# MRCS-Dual-3-Position-Semaphore-Controlle.net
KiCad netlist of a schematic drawn in EAGLE
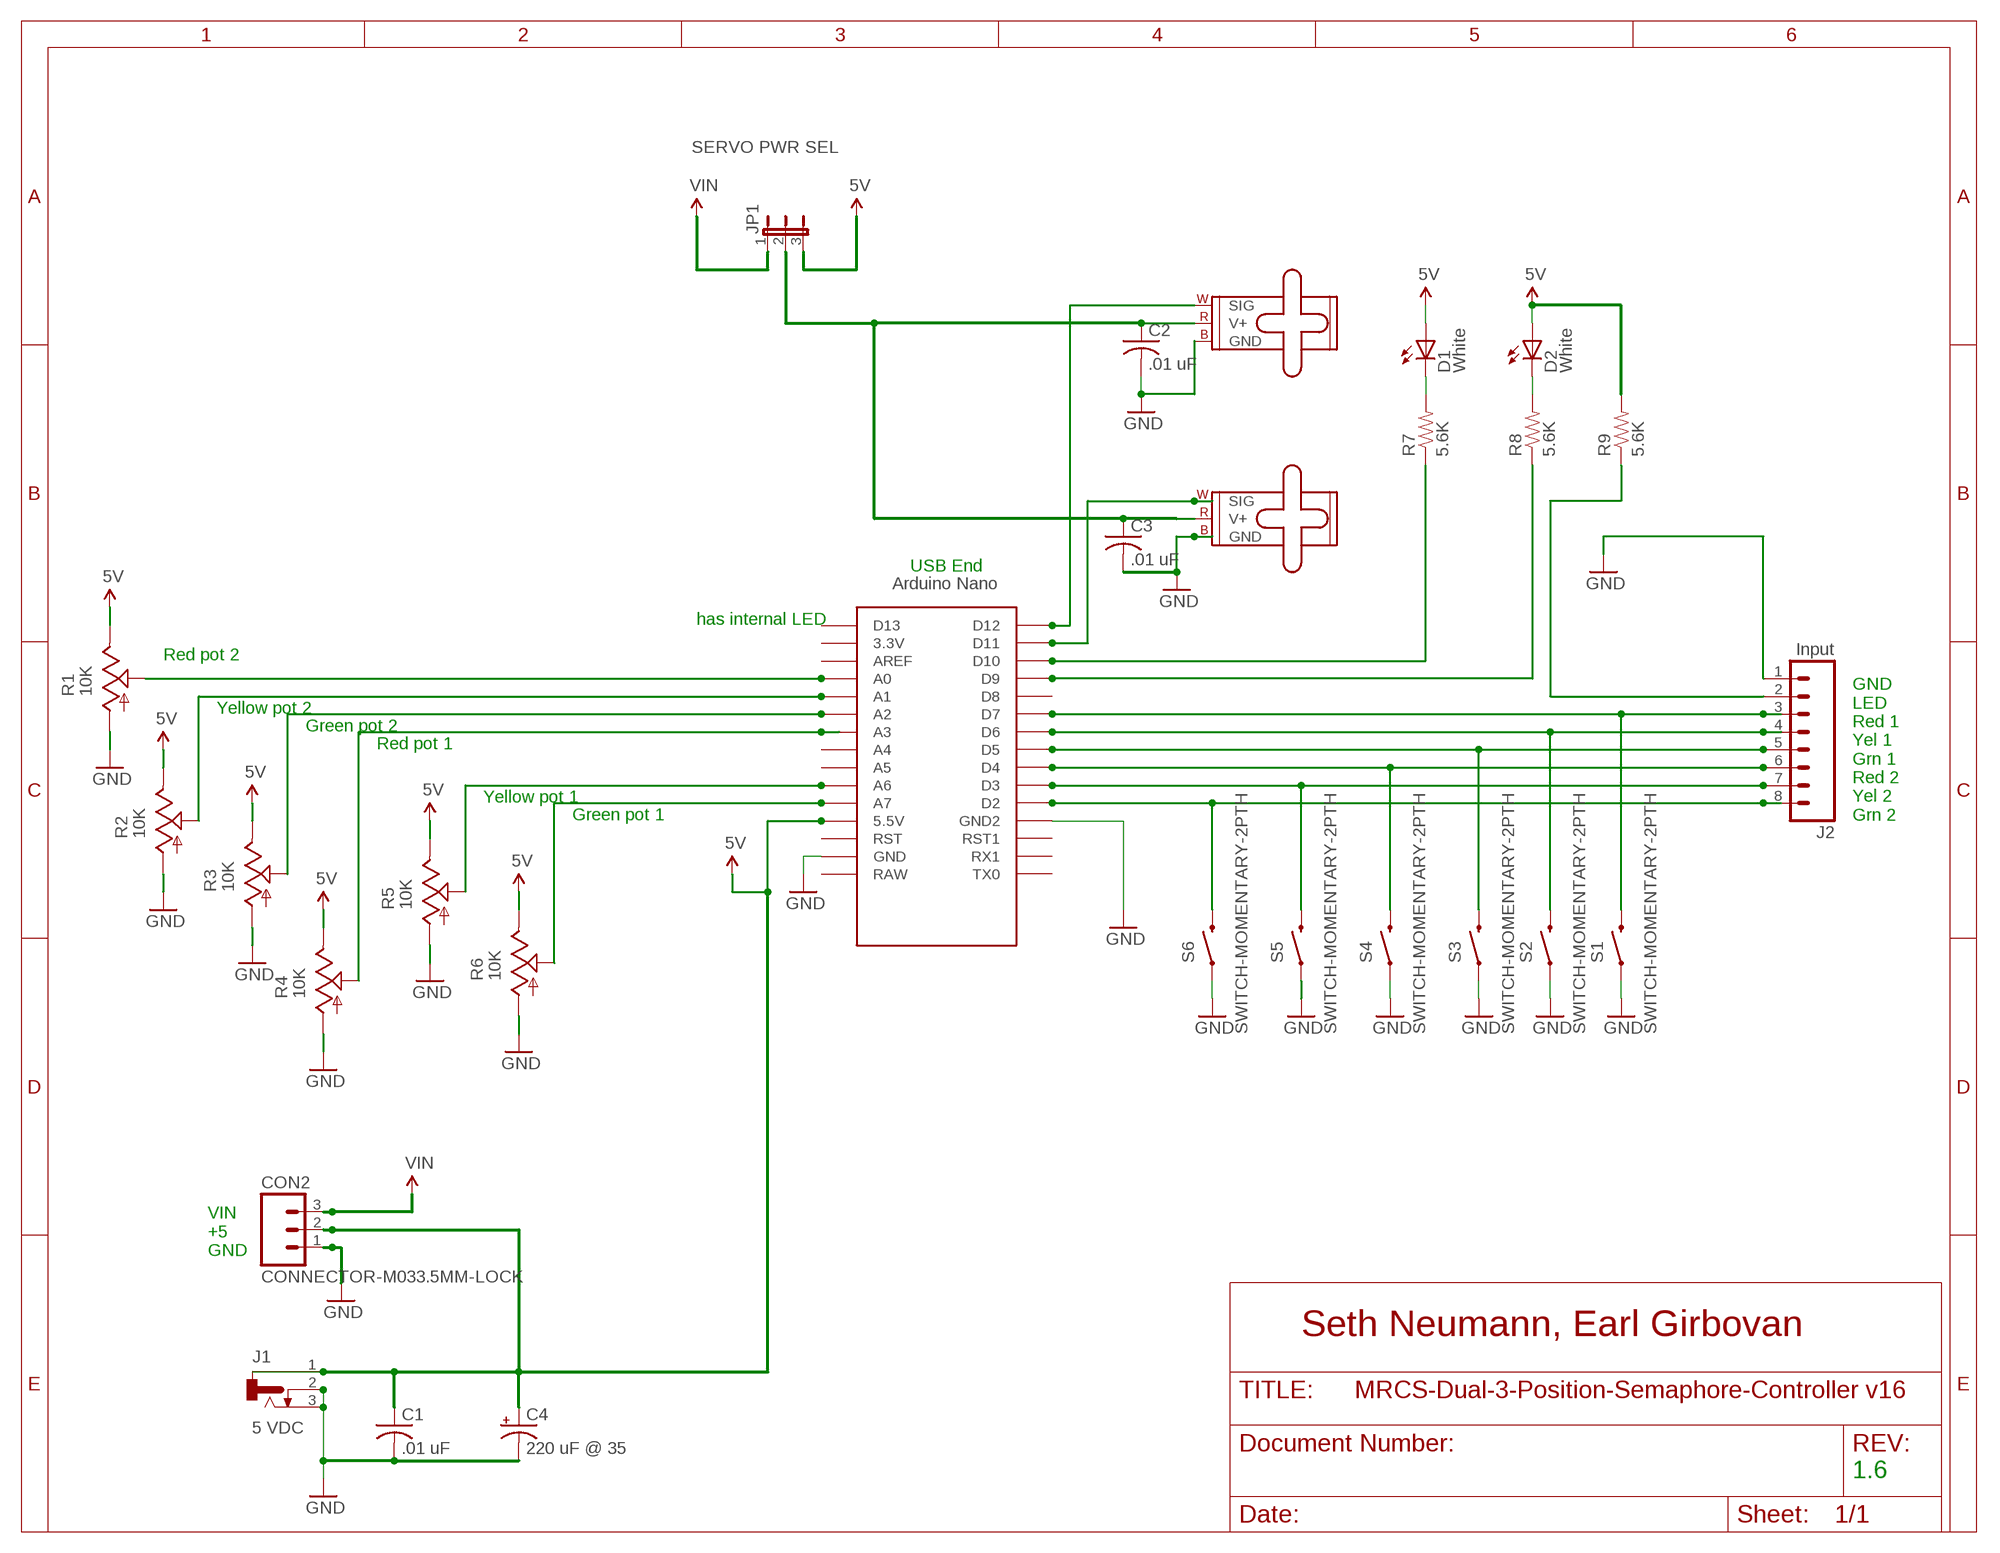
[diagram p0: schematic, sheet 1]

(export (version "E")
  (design (tool "Eeschema 10.0.6"))
  (components
    (comp (ref "C1")
      (value ".01 uF")
      (footprint "eagle-import:C050-024X044")
      (libsource (lib "eagle-import") (part "CAPPTH1"))
    )
    (comp (ref "C2")
      (value ".01 uF")
      (footprint "eagle-import:C050-024X044")
      (libsource (lib "eagle-import") (part "CAPPTH1"))
    )
    (comp (ref "C3")
      (value ".01 uF")
      (footprint "eagle-import:C050-024X044")
      (libsource (lib "eagle-import") (part "CAPPTH1"))
    )
    (comp (ref "C4")
      (value "220 uF @ 35")
      (footprint "eagle-import:E5-10.5")
      (libsource (lib "eagle-import") (part "CAP-POLPTH-5MM"))
    )
    (comp (ref "CON2")
      (value "CONNECTOR-M033.5MM-LOCK")
      (footprint "eagle-import:SCREWTERMINAL-3.5MM-3_LOCK.007S")
      (libsource (lib "eagle-import") (part "CONNECTOR-M033.5MM-LOCK"))
    )
    (comp (ref "D1")
      (value "White")
      (footprint "eagle-import:LED3MM")
      (libsource (lib "eagle-import") (part "LEDLED3MM"))
    )
    (comp (ref "D2")
      (value "White")
      (footprint "eagle-import:LED3MM")
      (libsource (lib "eagle-import") (part "LEDLED3MM"))
    )
    (comp (ref "J1")
      (value "5 VDC")
      (footprint "eagle-import:DCJ0202")
      (libsource (lib "eagle-import") (part "CONNECTOR-DC-POWER-RA"))
    )
    (comp (ref "J2")
      (value "Input")
      (footprint "eagle-import:1X08_LOCK")
      (libsource (lib "eagle-import") (part "CONNECTOR-M08LOCK"))
    )
    (comp (ref "JP1")
      (value "SERVO PWR SEL")
      (footprint "eagle-import:1X03")
      (libsource (lib "eagle-import") (part "JUMPER-3PTH-LOCK"))
    )
    (comp (ref "M1")
      (value "SMALL_SERVO")
      (footprint "eagle-import:1X03")
      (libsource (lib "eagle-import") (part "SMALL_SERVO"))
    )
    (comp (ref "M2")
      (value "SMALL_SERVO")
      (footprint "eagle-import:1X03")
      (libsource (lib "eagle-import") (part "SMALL_SERVO"))
    )
    (comp (ref "NANO")
      (value "NANO")
      (footprint "eagle-import:NANO")
      (libsource (lib "eagle-import") (part "NANO"))
    )
    (comp (ref "R1")
      (value "10K")
      (footprint "eagle-import:RS3")
      (libsource (lib "eagle-import") (part "TRIM_US-RS3"))
    )
    (comp (ref "R2")
      (value "10K")
      (footprint "eagle-import:RS3")
      (libsource (lib "eagle-import") (part "TRIM_US-RS3"))
    )
    (comp (ref "R3")
      (value "10K")
      (footprint "eagle-import:RS3")
      (libsource (lib "eagle-import") (part "TRIM_US-RS3"))
    )
    (comp (ref "R4")
      (value "10K")
      (footprint "eagle-import:RS3")
      (libsource (lib "eagle-import") (part "TRIM_US-RS3"))
    )
    (comp (ref "R5")
      (value "10K")
      (footprint "eagle-import:RS3")
      (libsource (lib "eagle-import") (part "TRIM_US-RS3"))
    )
    (comp (ref "R6")
      (value "10K")
      (footprint "eagle-import:RS3")
      (libsource (lib "eagle-import") (part "TRIM_US-RS3"))
    )
    (comp (ref "R7")
      (value "5.6K")
      (footprint "eagle-import:AXIAL-0.4")
      (libsource (lib "eagle-import") (part "RESISTORPTH-1/4W"))
    )
    (comp (ref "R8")
      (value "5.6K")
      (footprint "eagle-import:AXIAL-0.4")
      (libsource (lib "eagle-import") (part "RESISTORPTH-1/4W"))
    )
    (comp (ref "R9")
      (value "5.6K")
      (footprint "eagle-import:AXIAL-0.4")
      (libsource (lib "eagle-import") (part "RESISTORPTH-1/4W"))
    )
    (comp (ref "S1")
      (value "SWITCH-MOMENTARY-2PTH")
      (footprint "eagle-import:TACTILE-PTH")
      (libsource (lib "eagle-import") (part "SWITCH-MOMENTARY-2PTH"))
    )
    (comp (ref "S2")
      (value "SWITCH-MOMENTARY-2PTH")
      (footprint "eagle-import:TACTILE-PTH")
      (libsource (lib "eagle-import") (part "SWITCH-MOMENTARY-2PTH"))
    )
    (comp (ref "S3")
      (value "SWITCH-MOMENTARY-2PTH")
      (footprint "eagle-import:TACTILE-PTH")
      (libsource (lib "eagle-import") (part "SWITCH-MOMENTARY-2PTH"))
    )
    (comp (ref "S4")
      (value "SWITCH-MOMENTARY-2PTH")
      (footprint "eagle-import:TACTILE-PTH")
      (libsource (lib "eagle-import") (part "SWITCH-MOMENTARY-2PTH"))
    )
    (comp (ref "S5")
      (value "SWITCH-MOMENTARY-2PTH")
      (footprint "eagle-import:TACTILE-PTH")
      (libsource (lib "eagle-import") (part "SWITCH-MOMENTARY-2PTH"))
    )
    (comp (ref "S6")
      (value "SWITCH-MOMENTARY-2PTH")
      (footprint "eagle-import:TACTILE-PTH")
      (libsource (lib "eagle-import") (part "SWITCH-MOMENTARY-2PTH"))
    )
  )
  (nets
    (net (code "1") (name "5V") (class "Default")
      (node (ref "C1") (pin "1") (pinfunction "1_1") (pintype "passive"))
      (node (ref "C4") (pin "+") (pinfunction "+_+") (pintype "passive"))
      (node (ref "CON2") (pin "2") (pinfunction "2_2") (pintype "passive"))
      (node (ref "D1") (pin "A") (pinfunction "A_A") (pintype "passive"))
      (node (ref "D2") (pin "A") (pinfunction "A_A") (pintype "passive"))
      (node (ref "J1") (pin "1") (pinfunction "1_1") (pintype "passive"))
      (node (ref "JP1") (pin "3") (pinfunction "3_3") (pintype "passive"))
      (node (ref "NANO") (pin "5V") (pinfunction "5.5V_5V") (pintype "bidirectional"))
      (node (ref "R1") (pin "E") (pinfunction "E_E") (pintype "passive"))
      (node (ref "R2") (pin "E") (pinfunction "E_E") (pintype "passive"))
      (node (ref "R3") (pin "E") (pinfunction "E_E") (pintype "passive"))
      (node (ref "R4") (pin "E") (pinfunction "E_E") (pintype "passive"))
      (node (ref "R5") (pin "E") (pinfunction "E_E") (pintype "passive"))
      (node (ref "R6") (pin "E") (pinfunction "E_E") (pintype "passive"))
      (node (ref "R9") (pin "P$2") (pinfunction "2_P$2") (pintype "passive"))
    )
    (net (code "2") (name "GND") (class "Default")
      (node (ref "C1") (pin "2") (pinfunction "2_2") (pintype "passive"))
      (node (ref "C2") (pin "2") (pinfunction "2_2") (pintype "passive"))
      (node (ref "C3") (pin "2") (pinfunction "2_2") (pintype "passive"))
      (node (ref "C4") (pin "-") (pinfunction "-_-") (pintype "passive"))
      (node (ref "CON2") (pin "1") (pinfunction "1_1") (pintype "passive"))
      (node (ref "J1") (pin "2") (pinfunction "2_2") (pintype "passive"))
      (node (ref "J1") (pin "3") (pinfunction "3_3") (pintype "passive"))
      (node (ref "J2") (pin "1") (pinfunction "1_1") (pintype "passive"))
      (node (ref "M1") (pin "3") (pinfunction "GND_3") (pintype "bidirectional"))
      (node (ref "M2") (pin "3") (pinfunction "GND_3") (pintype "bidirectional"))
      (node (ref "NANO") (pin "GND") (pinfunction "GND_GND") (pintype "bidirectional"))
      (node (ref "NANO") (pin "GND1") (pinfunction "GND2_GND1") (pintype "bidirectional"))
      (node (ref "R1") (pin "A") (pinfunction "A_A") (pintype "passive"))
      (node (ref "R2") (pin "A") (pinfunction "A_A") (pintype "passive"))
      (node (ref "R3") (pin "A") (pinfunction "A_A") (pintype "passive"))
      (node (ref "R4") (pin "A") (pinfunction "A_A") (pintype "passive"))
      (node (ref "R5") (pin "A") (pinfunction "A_A") (pintype "passive"))
      (node (ref "R6") (pin "A") (pinfunction "A_A") (pintype "passive"))
      (node (ref "S1") (pin "1") (pinfunction "1_1") (pintype "passive"))
      (node (ref "S2") (pin "1") (pinfunction "1_1") (pintype "passive"))
      (node (ref "S3") (pin "1") (pinfunction "1_1") (pintype "passive"))
      (node (ref "S4") (pin "1") (pinfunction "1_1") (pintype "passive"))
      (node (ref "S5") (pin "1") (pinfunction "1_1") (pintype "passive"))
      (node (ref "S6") (pin "1") (pinfunction "1_1") (pintype "passive"))
    )
    (net (code "3") (name "Net-(D1-C)") (class "Default")
      (node (ref "D1") (pin "K") (pinfunction "C_K") (pintype "passive"))
      (node (ref "R7") (pin "P$2") (pinfunction "2_P$2") (pintype "passive"))
    )
    (net (code "4") (name "Net-(D2-C)") (class "Default")
      (node (ref "D2") (pin "K") (pinfunction "C_K") (pintype "passive"))
      (node (ref "R8") (pin "P$2") (pinfunction "2_P$2") (pintype "passive"))
    )
    (net (code "5") (name "Net-(M1-SIG)") (class "Default")
      (node (ref "M1") (pin "1") (pinfunction "SIG_1") (pintype "bidirectional"))
      (node (ref "NANO") (pin "D12") (pinfunction "D12_D12") (pintype "bidirectional"))
    )
    (net (code "6") (name "Net-(M1-V+)") (class "Default")
      (node (ref "C2") (pin "1") (pinfunction "1_1") (pintype "passive"))
      (node (ref "C3") (pin "1") (pinfunction "1_1") (pintype "passive"))
      (node (ref "JP1") (pin "2") (pinfunction "2_2") (pintype "passive"))
      (node (ref "M1") (pin "2") (pinfunction "V+_2") (pintype "bidirectional"))
      (node (ref "M2") (pin "2") (pinfunction "V+_2") (pintype "bidirectional"))
    )
    (net (code "7") (name "Net-(M2-SIG)") (class "Default")
      (node (ref "M2") (pin "1") (pinfunction "SIG_1") (pintype "bidirectional"))
      (node (ref "NANO") (pin "D11") (pinfunction "D11_D11") (pintype "bidirectional"))
    )
    (net (code "8") (name "Net-(NANO-PadA0)") (class "Default")
      (node (ref "NANO") (pin "A0") (pinfunction "A0_A0") (pintype "bidirectional"))
      (node (ref "R1") (pin "S") (pinfunction "S_S") (pintype "passive"))
    )
    (net (code "9") (name "Net-(NANO-PadA1)") (class "Default")
      (node (ref "NANO") (pin "A1") (pinfunction "A1_A1") (pintype "bidirectional"))
      (node (ref "R2") (pin "S") (pinfunction "S_S") (pintype "passive"))
    )
    (net (code "10") (name "Net-(NANO-PadA2)") (class "Default")
      (node (ref "NANO") (pin "A2") (pinfunction "A2_A2") (pintype "bidirectional"))
      (node (ref "R3") (pin "S") (pinfunction "S_S") (pintype "passive"))
    )
    (net (code "11") (name "Net-(NANO-PadA3)") (class "Default")
      (node (ref "NANO") (pin "A3") (pinfunction "A3_A3") (pintype "bidirectional"))
      (node (ref "R4") (pin "S") (pinfunction "S_S") (pintype "passive"))
    )
    (net (code "12") (name "Net-(NANO-PadA6)") (class "Default")
      (node (ref "NANO") (pin "A6") (pinfunction "A6_A6") (pintype "bidirectional"))
      (node (ref "R5") (pin "S") (pinfunction "S_S") (pintype "passive"))
    )
    (net (code "13") (name "Net-(NANO-PadA7)") (class "Default")
      (node (ref "NANO") (pin "A7") (pinfunction "A7_A7") (pintype "bidirectional"))
      (node (ref "R6") (pin "S") (pinfunction "S_S") (pintype "passive"))
    )
    (net (code "14") (name "Net-(R7-1)") (class "Default")
      (node (ref "NANO") (pin "D10") (pinfunction "D10_D10") (pintype "bidirectional"))
      (node (ref "R7") (pin "P$1") (pinfunction "1_P$1") (pintype "passive"))
    )
    (net (code "15") (name "Net-(R8-1)") (class "Default")
      (node (ref "NANO") (pin "D9") (pinfunction "D9_D9") (pintype "bidirectional"))
      (node (ref "R8") (pin "P$1") (pinfunction "1_P$1") (pintype "passive"))
    )
    (net (code "16") (name "Net-(R9-1)") (class "Default")
      (node (ref "J2") (pin "2") (pinfunction "2_2") (pintype "passive"))
      (node (ref "R9") (pin "P$1") (pinfunction "1_P$1") (pintype "passive"))
    )
    (net (code "17") (name "Net-(S1-2)") (class "Default")
      (node (ref "J2") (pin "3") (pinfunction "3_3") (pintype "passive"))
      (node (ref "NANO") (pin "D7") (pinfunction "D7_D7") (pintype "bidirectional"))
      (node (ref "S1") (pin "3") (pinfunction "2_3") (pintype "passive"))
    )
    (net (code "18") (name "Net-(S2-2)") (class "Default")
      (node (ref "J2") (pin "4") (pinfunction "4_4") (pintype "passive"))
      (node (ref "NANO") (pin "D6") (pinfunction "D6_D6") (pintype "bidirectional"))
      (node (ref "S2") (pin "3") (pinfunction "2_3") (pintype "passive"))
    )
    (net (code "19") (name "Net-(S3-2)") (class "Default")
      (node (ref "J2") (pin "5") (pinfunction "5_5") (pintype "passive"))
      (node (ref "NANO") (pin "D5") (pinfunction "D5_D5") (pintype "bidirectional"))
      (node (ref "S3") (pin "3") (pinfunction "2_3") (pintype "passive"))
    )
    (net (code "20") (name "Net-(S4-2)") (class "Default")
      (node (ref "J2") (pin "6") (pinfunction "6_6") (pintype "passive"))
      (node (ref "NANO") (pin "D4") (pinfunction "D4_D4") (pintype "bidirectional"))
      (node (ref "S4") (pin "3") (pinfunction "2_3") (pintype "passive"))
    )
    (net (code "21") (name "Net-(S5-2)") (class "Default")
      (node (ref "J2") (pin "7") (pinfunction "7_7") (pintype "passive"))
      (node (ref "NANO") (pin "D3") (pinfunction "D3_D3") (pintype "bidirectional"))
      (node (ref "S5") (pin "3") (pinfunction "2_3") (pintype "passive"))
    )
    (net (code "22") (name "Net-(S6-2)") (class "Default")
      (node (ref "J2") (pin "8") (pinfunction "8_8") (pintype "passive"))
      (node (ref "NANO") (pin "D2") (pinfunction "D2_D2") (pintype "bidirectional"))
      (node (ref "S6") (pin "3") (pinfunction "2_3") (pintype "passive"))
    )
    (net (code "23") (name "VIN") (class "Default")
      (node (ref "CON2") (pin "3") (pinfunction "3_3") (pintype "passive"))
      (node (ref "JP1") (pin "1") (pinfunction "1_1") (pintype "passive"))
    )
    (net (code "24") (name "unconnected-(NANO-Pad3.3V)") (class "Default")
      (node (ref "NANO") (pin "3.3V") (pinfunction "3.3V_3.3V") (pintype "bidirectional"))
    )
    (net (code "25") (name "unconnected-(NANO-PadA4)") (class "Default")
      (node (ref "NANO") (pin "A4") (pinfunction "A4_A4") (pintype "bidirectional"))
    )
    (net (code "26") (name "unconnected-(NANO-PadA5)") (class "Default")
      (node (ref "NANO") (pin "A5") (pinfunction "A5_A5") (pintype "bidirectional"))
    )
    (net (code "27") (name "unconnected-(NANO-PadAREF)") (class "Default")
      (node (ref "NANO") (pin "AREF") (pinfunction "AREF_AREF") (pintype "bidirectional"))
    )
    (net (code "28") (name "unconnected-(NANO-PadD8)") (class "Default")
      (node (ref "NANO") (pin "D8") (pinfunction "D8_D8") (pintype "bidirectional"))
    )
    (net (code "29") (name "unconnected-(NANO-PadD13)") (class "Default")
      (node (ref "NANO") (pin "D13") (pinfunction "D13_D13") (pintype "bidirectional"))
    )
    (net (code "30") (name "unconnected-(NANO-PadRAW)") (class "Default")
      (node (ref "NANO") (pin "RAW") (pinfunction "RAW_RAW") (pintype "bidirectional"))
    )
    (net (code "31") (name "unconnected-(NANO-PadRST)") (class "Default")
      (node (ref "NANO") (pin "RST") (pinfunction "RST_RST") (pintype "bidirectional"))
    )
    (net (code "32") (name "unconnected-(NANO-PadRST1)") (class "Default")
      (node (ref "NANO") (pin "RST1") (pinfunction "RST1_RST1") (pintype "bidirectional"))
    )
    (net (code "33") (name "unconnected-(NANO-PadRX1)") (class "Default")
      (node (ref "NANO") (pin "RX1") (pinfunction "RX1_RX1") (pintype "bidirectional"))
    )
    (net (code "34") (name "unconnected-(NANO-PadTX0)") (class "Default")
      (node (ref "NANO") (pin "TX0") (pinfunction "TX0_TX0") (pintype "bidirectional"))
    )
  )
)
